# POWER_IN.net
KiCad netlist of a schematic drawn in Altium Designer
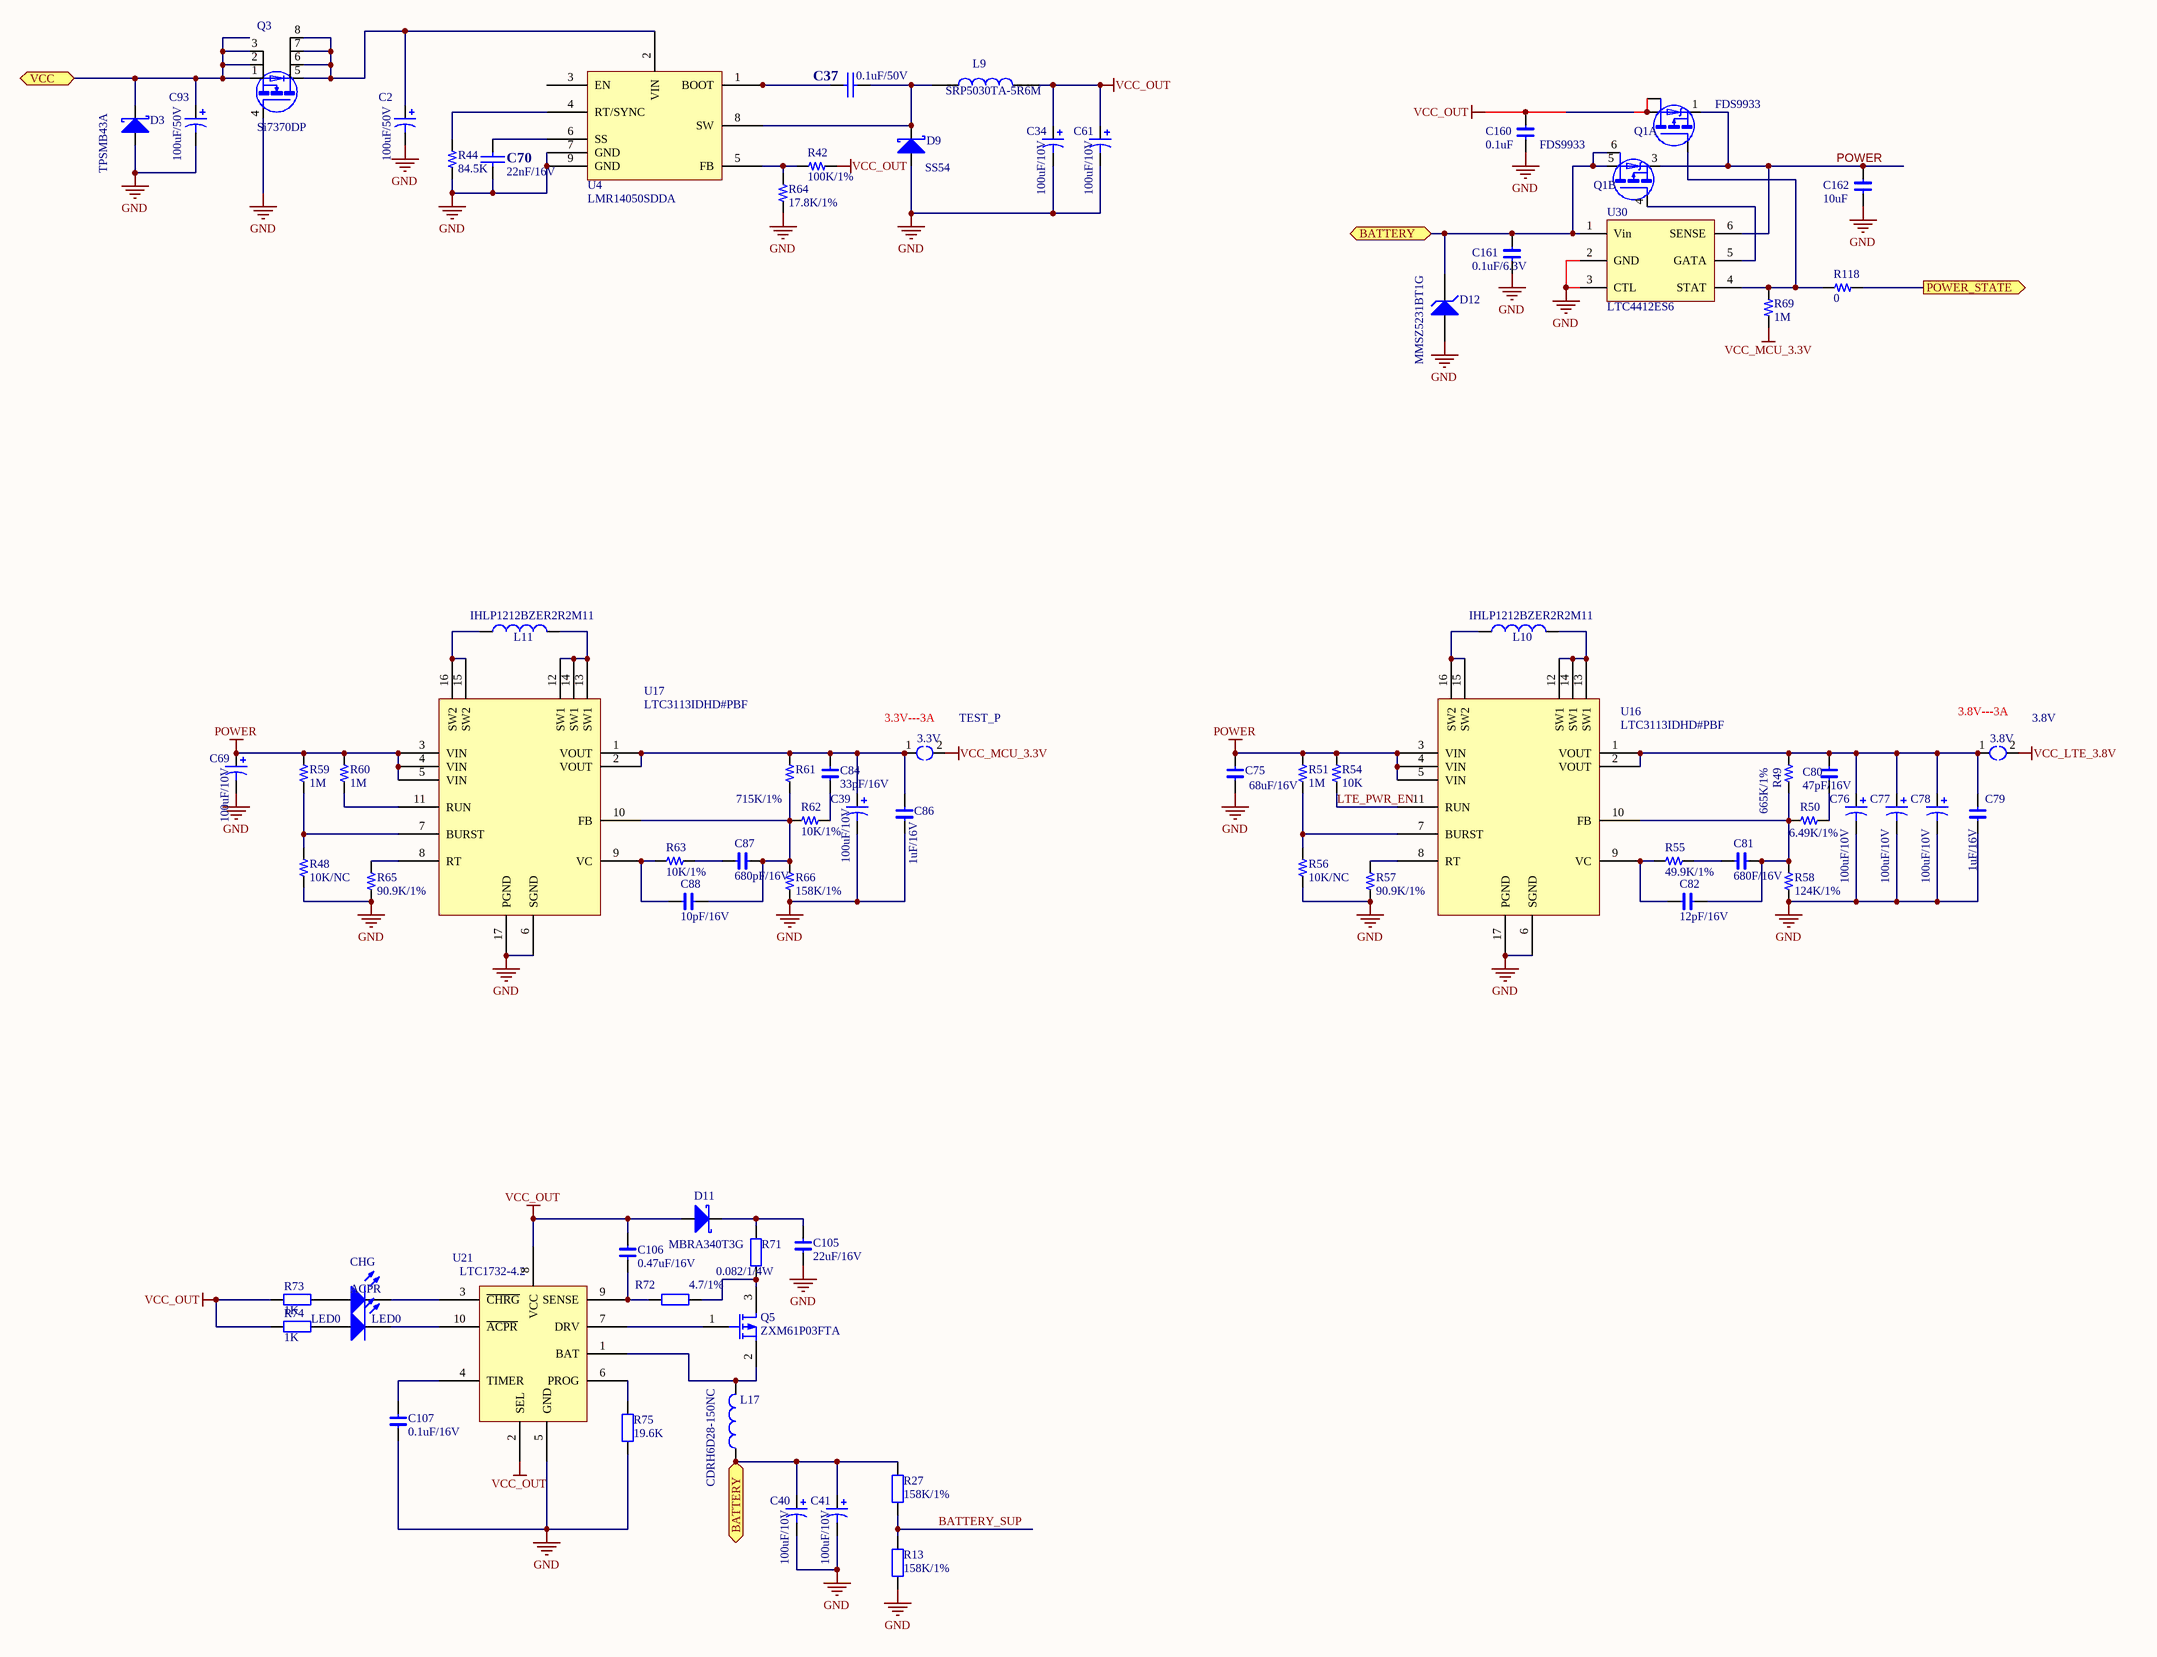
[diagram p0: POWER_IN.SchDoc]

(export (version "E")
  (design (tool "Eeschema 10.0.6"))
  (components
    (comp (ref "3.3V")
      (value "TEST_P")
      (footprint "Pcblib_20110825:TP_High PWR")
      (libsource (lib "Schlib_20110825") (part "TEST_P"))
    )
    (comp (ref "3.8V")
      (value "3.8V")
      (footprint "Pcblib_20110825:TP_High PWR")
      (description "TEST_P")
      (libsource (lib "Schlib_20110825") (part "TEST_P"))
    )
    (comp (ref "ACPR")
      (value "LED0")
      (footprint "0603LED")
      (description "Typical INFRARED GaAs LED")
      (fields (field (name "PUBLISHER") "Altium Limited"))
      (libsource (lib "Miscellaneous Devices") (part "LED0"))
    )
    (comp (ref "C2")
      (value "100uF/50V")
      (footprint "2220C")
      (description "Polarized Capacitor (Radial)")
      (fields (field (name "PUBLISHER") "Altium Limited"))
      (libsource (lib "Miscellaneous Devices") (part "Cap Pol1"))
    )
    (comp (ref "C34")
      (value "100uF/10V")
      (footprint "1210E")
      (description "Polarized Capacitor (Radial)")
      (fields (field (name "PUBLISHER") "Altium Limited"))
      (libsource (lib "Miscellaneous Devices") (part "Cap Pol1"))
    )
    (comp (ref "C37")
      (value "0.1uF/50V")
      (footprint "0603C")
      (description "Capacitor")
      (libsource (lib "*") (part "CAP"))
    )
    (comp (ref "C39")
      (value "100uF/10V")
      (footprint "1210E")
      (description "Polarized Capacitor (Radial)")
      (fields (field (name "PUBLISHER") "Altium Limited"))
      (libsource (lib "Miscellaneous Devices") (part "Cap Pol1"))
    )
    (comp (ref "C40")
      (value "100uF/10V")
      (footprint "1210E")
      (description "Polarized Capacitor (Radial)")
      (fields (field (name "PUBLISHER") "Altium Limited"))
      (libsource (lib "Miscellaneous Devices") (part "Cap Pol1"))
    )
    (comp (ref "C41")
      (value "100uF/10V")
      (footprint "1210E")
      (description "Polarized Capacitor (Radial)")
      (fields (field (name "PUBLISHER") "Altium Limited"))
      (libsource (lib "Miscellaneous Devices") (part "Cap Pol1"))
    )
    (comp (ref "C61")
      (value "100uF/10V")
      (footprint "1210E")
      (description "Polarized Capacitor (Radial)")
      (fields (field (name "PUBLISHER") "Altium Limited"))
      (libsource (lib "Miscellaneous Devices") (part "Cap Pol1"))
    )
    (comp (ref "C69")
      (value "100uF/10V")
      (footprint "1210E")
      (description "Polarized Capacitor (Radial)")
      (fields (field (name "PUBLISHER") "Altium Limited"))
      (libsource (lib "Miscellaneous Devices") (part "Cap Pol1"))
    )
    (comp (ref "C70")
      (value "22nF/16V")
      (footprint "0603C")
      (description "Capacitor")
      (libsource (lib "*") (part "CAP"))
    )
    (comp (ref "C75")
      (value "68uF/16V")
      (footprint "1206C")
      (description "C")
      (libsource (lib "Top") (part "C"))
    )
    (comp (ref "C76")
      (value "100uF/10V")
      (footprint "1210E")
      (description "Polarized Capacitor (Radial)")
      (fields (field (name "PUBLISHER") "Altium Limited"))
      (libsource (lib "Miscellaneous Devices") (part "Cap Pol1"))
    )
    (comp (ref "C77")
      (value "100uF/10V")
      (footprint "1210E")
      (description "Polarized Capacitor (Radial)")
      (fields (field (name "PUBLISHER") "Altium Limited"))
      (libsource (lib "Miscellaneous Devices") (part "Cap Pol1"))
    )
    (comp (ref "C78")
      (value "100uF/10V")
      (footprint "1210E")
      (description "Polarized Capacitor (Radial)")
      (fields (field (name "PUBLISHER") "Altium Limited"))
      (libsource (lib "Miscellaneous Devices") (part "Cap Pol1"))
    )
    (comp (ref "C79")
      (value "1uF/16V")
      (footprint "0603C")
      (description "C")
      (libsource (lib "Top") (part "C"))
    )
    (comp (ref "C80")
      (value "47pF/16V")
      (footprint "0603C")
      (description "C")
      (libsource (lib "Top") (part "C"))
    )
    (comp (ref "C81")
      (value "680F/16V")
      (footprint "0603C")
      (description "C")
      (libsource (lib "Top") (part "C"))
    )
    (comp (ref "C82")
      (value "12pF/16V")
      (footprint "0603C")
      (description "C")
      (libsource (lib "Top") (part "C"))
    )
    (comp (ref "C84")
      (value "33pF/16V")
      (footprint "0603C")
      (description "C")
      (libsource (lib "Top") (part "C"))
    )
    (comp (ref "C86")
      (value "1uF/16V")
      (footprint "0603C")
      (description "C")
      (libsource (lib "Top") (part "C"))
    )
    (comp (ref "C87")
      (value "680pF/16V")
      (footprint "0603C")
      (description "C")
      (libsource (lib "Top") (part "C"))
    )
    (comp (ref "C88")
      (value "10pF/16V")
      (footprint "0603C")
      (description "C")
      (libsource (lib "Top") (part "C"))
    )
    (comp (ref "C93")
      (value "100uF/50V")
      (footprint "2220C")
      (description "Polarized Capacitor (Radial)")
      (fields (field (name "PUBLISHER") "Altium Limited"))
      (libsource (lib "Miscellaneous Devices") (part "Cap Pol1"))
    )
    (comp (ref "C105")
      (value "22uF/16V")
      (footprint "0805C")
      (description "C")
      (libsource (lib "Top") (part "C"))
    )
    (comp (ref "C106")
      (value "0.47uF/16V")
      (footprint "0603C")
      (description "C")
      (libsource (lib "Top") (part "C"))
    )
    (comp (ref "C107")
      (value "0.1uF/16V")
      (footprint "0603C")
      (description "C")
      (libsource (lib "Top") (part "C"))
    )
    (comp (ref "C160") (value "0.1uF") (footprint "0603C") (description "C") (libsource (lib "*") (part "C")))
    (comp (ref "C161")
      (value "0.1uF/6.3V")
      (footprint "0603C")
      (description "C")
      (libsource (lib "*") (part "C"))
    )
    (comp (ref "C162") (value "10uF") (footprint "0603C") (description "C") (libsource (lib "*") (part "C")))
    (comp (ref "CHG")
      (value "LED0")
      (footprint "0603LED")
      (description "Typical INFRARED GaAs LED")
      (fields (field (name "PUBLISHER") "Altium Limited"))
      (libsource (lib "Miscellaneous Devices") (part "LED0"))
    )
    (comp (ref "D3")
      (value "TPSMB43A")
      (footprint "Pcblib_20110825:SMB")
      (description "Schottky Diode")
      (libsource (lib "*") (part "DIODE S"))
    )
    (comp (ref "D9")
      (value "SS54")
      (footprint "SMa")
      (description "Schottky Diode")
      (libsource (lib "*") (part "DIODE S"))
    )
    (comp (ref "D11")
      (value "MBRA340T3G")
      (footprint "SMA")
      (description "Schottky Diode")
      (libsource (lib "*") (part "DIODE S"))
    )
    (comp (ref "D12")
      (value "MMSZ5231BT1G")
      (footprint "Pcblib_20110825:SOD123")
      (description "Zener Diode")
      (fields (field (name "PUBLISHER") "Altium Limited"))
      (libsource (lib "Miscellaneous Devices") (part "D Zener"))
    )
    (comp (ref "L9") (value "SRP5030TA-5R6M") (footprint "SRP5030T") (libsource (lib "*") (part "INDUCTOR")))
    (comp (ref "L10")
      (value "IHLP1212BZER2R2M11")
      (footprint "Pcblib_20110825:IHLP-1212BZ")
      (description "Inductor")
      (fields (field (name "PUBLISHER") "Altium Limited"))
      (libsource (lib "Miscellaneous Devices") (part "Inductor"))
    )
    (comp (ref "L11")
      (value "IHLP1212BZER2R2M11")
      (footprint "Pcblib_20110825:IHLP-1212BZ")
      (description "Inductor")
      (fields (field (name "PUBLISHER") "Altium Limited"))
      (libsource (lib "Miscellaneous Devices") (part "Inductor"))
    )
    (comp (ref "L17")
      (value "CDRH6D28-150NC")
      (footprint "Pcblib_20110825:CDRH6D23")
      (description "Inductor")
      (fields (field (name "PUBLISHER") "Altium Limited"))
      (libsource (lib "Miscellaneous Devices") (part "Inductor"))
    )
    (comp (ref "Q1") (value "FDS9933") (footprint "FDS9933") (libsource (lib "*") (part "FDS4935")))
    (comp (ref "Q3")
      (value "Si7370DP")
      (footprint "PowerPAK SO-8")
      (libsource (lib "stm32") (part "BSC070N1ONS3"))
    )
    (comp (ref "Q5")
      (value "ZXM61P03FTA")
      (footprint "SOT23-3")
      (description "ZXM61P03F")
      (fields (field (name "PUBLISHER") "Altium Limited"))
      (libsource (lib "Miscellaneous Devices") (part "MOSFET-P"))
    )
    (comp (ref "R13")
      (value "158K/1%")
      (footprint "0603R")
      (description "Resistor")
      (fields (field (name "PUBLISHER") "Altium Limited"))
      (libsource (lib "") (part "Res2_1"))
    )
    (comp (ref "R27")
      (value "158K/1%")
      (footprint "0603R")
      (description "Resistor")
      (fields (field (name "PUBLISHER") "Altium Limited"))
      (libsource (lib "") (part "Res2_1"))
    )
    (comp (ref "R42")
      (value "100K/1%")
      (footprint "0603R")
      (description "R")
      (libsource (lib "JRJ_1") (part "R"))
    )
    (comp (ref "R44")
      (value "84.5K")
      (footprint "0603R")
      (description "R")
      (libsource (lib "JRJ_1") (part "R"))
    )
    (comp (ref "R48")
      (value "10K/NC")
      (footprint "0603R")
      (description "R")
      (libsource (lib "JRJ_1") (part "R"))
    )
    (comp (ref "R49")
      (value "665K/1%")
      (footprint "0603R")
      (description "R")
      (libsource (lib "JRJ_1") (part "R"))
    )
    (comp (ref "R50")
      (value "6.49K/1%")
      (footprint "0603R")
      (description "R")
      (libsource (lib "JRJ_1") (part "R"))
    )
    (comp (ref "R51") (value "1M") (footprint "0603R") (description "R") (libsource (lib "JRJ_1") (part "R")))
    (comp (ref "R54")
      (value "10K")
      (footprint "0603R")
      (description "R")
      (libsource (lib "JRJ_1") (part "R"))
    )
    (comp (ref "R55")
      (value "49.9K/1%")
      (footprint "0603R")
      (description "R")
      (libsource (lib "JRJ_1") (part "R"))
    )
    (comp (ref "R56")
      (value "10K/NC")
      (footprint "0603R")
      (description "R")
      (libsource (lib "JRJ_1") (part "R"))
    )
    (comp (ref "R57")
      (value "90.9K/1%")
      (footprint "0603R")
      (description "R")
      (libsource (lib "JRJ_1") (part "R"))
    )
    (comp (ref "R58")
      (value "124K/1%")
      (footprint "0603R")
      (description "R")
      (libsource (lib "JRJ_1") (part "R"))
    )
    (comp (ref "R59") (value "1M") (footprint "0603R") (description "R") (libsource (lib "JRJ_1") (part "R")))
    (comp (ref "R60") (value "1M") (footprint "0603R") (description "R") (libsource (lib "JRJ_1") (part "R")))
    (comp (ref "R61")
      (value "715K/1%")
      (footprint "0603R")
      (description "R")
      (libsource (lib "JRJ_1") (part "R"))
    )
    (comp (ref "R62")
      (value "10K/1%")
      (footprint "0603R")
      (description "R")
      (libsource (lib "JRJ_1") (part "R"))
    )
    (comp (ref "R63")
      (value "10K/1%")
      (footprint "0603R")
      (description "R")
      (libsource (lib "JRJ_1") (part "R"))
    )
    (comp (ref "R64")
      (value "17.8K/1%")
      (footprint "0603R")
      (description "R")
      (libsource (lib "JRJ_1") (part "R"))
    )
    (comp (ref "R65")
      (value "90.9K/1%")
      (footprint "0603R")
      (description "R")
      (libsource (lib "JRJ_1") (part "R"))
    )
    (comp (ref "R66")
      (value "158K/1%")
      (footprint "0603R")
      (description "R")
      (libsource (lib "JRJ_1") (part "R"))
    )
    (comp (ref "R69") (value "1M") (footprint "0603R") (description "R") (libsource (lib "*") (part "R")))
    (comp (ref "R71")
      (value "0.082/1/4W")
      (footprint "2010R")
      (description "Resistor")
      (fields (field (name "PUBLISHER") "Altium Limited"))
      (libsource (lib "") (part "Res2_1"))
    )
    (comp (ref "R72")
      (value "4.7/1%")
      (footprint "0603R")
      (description "Resistor")
      (fields (field (name "PUBLISHER") "Altium Limited"))
      (libsource (lib "Miscellaneous Devices") (part "Res2"))
    )
    (comp (ref "R73")
      (value "1K")
      (footprint "0603R")
      (description "Resistor")
      (fields (field (name "PUBLISHER") "Altium Limited"))
      (libsource (lib "") (part "Res2_2"))
    )
    (comp (ref "R74")
      (value "1K")
      (footprint "0603R")
      (description "Resistor")
      (fields (field (name "PUBLISHER") "Altium Limited"))
      (libsource (lib "") (part "Res2_2"))
    )
    (comp (ref "R75")
      (value "19.6K")
      (footprint "0603R")
      (description "Resistor")
      (fields (field (name "PUBLISHER") "Altium Limited"))
      (libsource (lib "") (part "Res2_1"))
    )
    (comp (ref "R118") (value "0") (footprint "0603R") (description "R") (libsource (lib "") (part "R_1")))
    (comp (ref "U4")
      (value "LMR14050SDDA")
      (footprint "SOP127P600X168_HS-8N")
      (libsource (lib "Schlib_20110825") (part "LMR14050SDDA"))
    )
    (comp (ref "U16")
      (value "LTC3113IDHD#PBF")
      (footprint "QFN50P400X500X80-16N")
      (libsource (lib "Schlib_20110825") (part "LTC3113IDHD#PBF"))
    )
    (comp (ref "U17")
      (value "LTC3113IDHD#PBF")
      (footprint "QFN50P400X500X80-16N")
      (libsource (lib "Schlib_20110825") (part "LTC3113IDHD#PBF"))
    )
    (comp (ref "U21")
      (value "LTC1732-4.2")
      (footprint "MSOP-10")
      (libsource (lib "Schlib_20110825") (part "LTC1732-4.2"))
    )
    (comp (ref "U30") (value "LTC4412ES6") (footprint "TSOT-23") (libsource (lib "*") (part "LTC4412")))
  )
  (nets
    (net (code "1") (name "/BATTERY") (class "Default")
      (node (ref "C161") (pin "2") (pintype "passive"))
      (node (ref "C40") (pin "1") (pinfunction "1_1") (pintype "passive"))
      (node (ref "C41") (pin "1") (pinfunction "1_1") (pintype "passive"))
      (node (ref "D12") (pin "K") (pinfunction "K_K") (pintype "passive"))
      (node (ref "L17") (pin "1") (pinfunction "1_1") (pintype "passive"))
      (node (ref "Q1") (pin "5") (pinfunction "D_5") (pintype "passive"))
      (node (ref "R27") (pin "2") (pinfunction "2_2") (pintype "passive"))
      (node (ref "U30") (pin "1") (pinfunction "Vin_1") (pintype "passive"))
    )
    (net (code "2") (name "/BATTERY_SUP") (class "Default")
      (node (ref "R13") (pin "2") (pinfunction "2_2") (pintype "passive"))
      (node (ref "R27") (pin "1") (pinfunction "1_1") (pintype "passive"))
    )
    (net (code "3") (name "/LTE_PWR_EN") (class "Default")
      (node (ref "R54") (pin "2") (pintype "passive"))
      (node (ref "U16") (pin "11") (pinfunction "RUN_11") (pintype "passive"))
    )
    (net (code "4") (name "/POWER_STATE") (class "Default") (node (ref "R118") (pin "2") (pintype "passive")))
    (net (code "5") (name "/VCC") (class "Default")
      (node (ref "C93") (pin "1") (pinfunction "1_1") (pintype "passive"))
      (node (ref "D3") (pin "2") (pinfunction "K_2") (pintype "passive"))
      (node (ref "Q3") (pin "1") (pinfunction "D_1") (pintype "passive"))
      (node (ref "Q3") (pin "2") (pinfunction "D_2") (pintype "passive"))
      (node (ref "Q3") (pin "3") (pinfunction "D_3") (pintype "passive"))
    )
    (net (code "6") (name "GND") (class "Default")
      (node (ref "C105") (pin "1") (pintype "passive"))
      (node (ref "C107") (pin "1") (pintype "passive"))
      (node (ref "C160") (pin "1") (pintype "passive"))
      (node (ref "C161") (pin "1") (pintype "passive"))
      (node (ref "C162") (pin "1") (pintype "passive"))
      (node (ref "C2") (pin "2") (pinfunction "2_2") (pintype "passive"))
      (node (ref "C34") (pin "2") (pinfunction "2_2") (pintype "passive"))
      (node (ref "C39") (pin "2") (pinfunction "2_2") (pintype "passive"))
      (node (ref "C40") (pin "2") (pinfunction "2_2") (pintype "passive"))
      (node (ref "C41") (pin "2") (pinfunction "2_2") (pintype "passive"))
      (node (ref "C61") (pin "2") (pinfunction "2_2") (pintype "passive"))
      (node (ref "C69") (pin "2") (pinfunction "2_2") (pintype "passive"))
      (node (ref "C70") (pin "2") (pinfunction "2_2") (pintype "passive"))
      (node (ref "C75") (pin "2") (pintype "passive"))
      (node (ref "C76") (pin "2") (pinfunction "2_2") (pintype "passive"))
      (node (ref "C77") (pin "2") (pinfunction "2_2") (pintype "passive"))
      (node (ref "C78") (pin "2") (pinfunction "2_2") (pintype "passive"))
      (node (ref "C79") (pin "2") (pintype "passive"))
      (node (ref "C86") (pin "2") (pintype "passive"))
      (node (ref "C93") (pin "2") (pinfunction "2_2") (pintype "passive"))
      (node (ref "D12") (pin "A") (pinfunction "A_A") (pintype "passive"))
      (node (ref "D3") (pin "1") (pinfunction "A_1") (pintype "passive"))
      (node (ref "D9") (pin "1") (pinfunction "A_1") (pintype "passive"))
      (node (ref "Q3") (pin "4") (pinfunction "G_4") (pintype "passive"))
      (node (ref "R13") (pin "1") (pinfunction "1_1") (pintype "passive"))
      (node (ref "R44") (pin "1") (pintype "passive"))
      (node (ref "R48") (pin "2") (pintype "passive"))
      (node (ref "R56") (pin "2") (pintype "passive"))
      (node (ref "R57") (pin "2") (pintype "passive"))
      (node (ref "R58") (pin "1") (pintype "passive"))
      (node (ref "R64") (pin "2") (pintype "passive"))
      (node (ref "R65") (pin "2") (pintype "passive"))
      (node (ref "R66") (pin "1") (pintype "passive"))
      (node (ref "R75") (pin "1") (pinfunction "1_1") (pintype "passive"))
      (node (ref "U16") (pin "17") (pinfunction "PGND_17") (pintype "passive"))
      (node (ref "U16") (pin "6") (pinfunction "SGND_6") (pintype "passive"))
      (node (ref "U17") (pin "17") (pinfunction "PGND_17") (pintype "passive"))
      (node (ref "U17") (pin "6") (pinfunction "SGND_6") (pintype "passive"))
      (node (ref "U21") (pin "5") (pinfunction "GND_5") (pintype "passive"))
      (node (ref "U30") (pin "2") (pinfunction "GND_2") (pintype "passive"))
      (node (ref "U30") (pin "3") (pinfunction "CTL_3") (pintype "passive"))
      (node (ref "U4") (pin "7") (pinfunction "GND_7") (pintype "passive"))
      (node (ref "U4") (pin "9") (pinfunction "GND_9") (pintype "passive"))
    )
    (net (code "7") (name "Net-(3.3V-Pad1)") (class "Default")
      (node (ref "3.3V") (pin "1") (pinfunction "1_1") (pintype "passive"))
      (node (ref "C39") (pin "1") (pinfunction "1_1") (pintype "passive"))
      (node (ref "C84") (pin "1") (pintype "passive"))
      (node (ref "C86") (pin "1") (pintype "passive"))
      (node (ref "R61") (pin "2") (pintype "passive"))
      (node (ref "U17") (pin "1") (pinfunction "VOUT_1") (pintype "passive"))
      (node (ref "U17") (pin "2") (pinfunction "VOUT_2") (pintype "passive"))
    )
    (net (code "8") (name "Net-(3.8V-Pad1)") (class "Default")
      (node (ref "3.8V") (pin "1") (pinfunction "1_1") (pintype "passive"))
      (node (ref "C76") (pin "1") (pinfunction "1_1") (pintype "passive"))
      (node (ref "C77") (pin "1") (pinfunction "1_1") (pintype "passive"))
      (node (ref "C78") (pin "1") (pinfunction "1_1") (pintype "passive"))
      (node (ref "C79") (pin "1") (pintype "passive"))
      (node (ref "C80") (pin "1") (pintype "passive"))
      (node (ref "R49") (pin "2") (pintype "passive"))
      (node (ref "U16") (pin "1") (pinfunction "VOUT_1") (pintype "passive"))
      (node (ref "U16") (pin "2") (pinfunction "VOUT_2") (pintype "passive"))
    )
    (net (code "9") (name "Net-(ACPR-A)") (class "Default")
      (node (ref "ACPR") (pin "1") (pinfunction "A_1") (pintype "passive"))
      (node (ref "R74") (pin "2") (pinfunction "2_2") (pintype "passive"))
    )
    (net (code "10") (name "Net-(ACPR-K)") (class "Default")
      (node (ref "ACPR") (pin "2") (pinfunction "K_2") (pintype "passive"))
      (node (ref "U21") (pin "10") (pinfunction "~{ACPR}_10") (pintype "passive"))
    )
    (net (code "11") (name "Net-(C80-Pad2)") (class "Default")
      (node (ref "C80") (pin "2") (pintype "passive"))
      (node (ref "R50") (pin "1") (pintype "passive"))
    )
    (net (code "12") (name "Net-(C81-Pad1)") (class "Default")
      (node (ref "C81") (pin "1") (pintype "passive"))
      (node (ref "R55") (pin "1") (pintype "passive"))
    )
    (net (code "13") (name "Net-(C84-Pad2)") (class "Default")
      (node (ref "C84") (pin "2") (pintype "passive"))
      (node (ref "R62") (pin "1") (pintype "passive"))
    )
    (net (code "14") (name "Net-(C87-Pad1)") (class "Default")
      (node (ref "C87") (pin "1") (pintype "passive"))
      (node (ref "R63") (pin "1") (pintype "passive"))
    )
    (net (code "15") (name "Net-(CHG-A)") (class "Default")
      (node (ref "CHG") (pin "1") (pinfunction "A_1") (pintype "passive"))
      (node (ref "R73") (pin "2") (pinfunction "2_2") (pintype "passive"))
    )
    (net (code "16") (name "Net-(CHG-K)") (class "Default")
      (node (ref "CHG") (pin "2") (pinfunction "K_2") (pintype "passive"))
      (node (ref "U21") (pin "3") (pinfunction "~{CHRG}_3") (pintype "passive"))
    )
    (net (code "17") (name "Net-(D9-K)") (class "Default")
      (node (ref "C37") (pin "1") (pinfunction "1_1") (pintype "passive"))
      (node (ref "D9") (pin "2") (pinfunction "K_2") (pintype "passive"))
      (node (ref "L9") (pin "1") (pinfunction "1_1") (pintype "passive"))
      (node (ref "U4") (pin "8") (pinfunction "SW_8") (pintype "passive"))
    )
    (net (code "18") (name "Net-(D11-K)") (class "Default")
      (node (ref "C105") (pin "2") (pintype "passive"))
      (node (ref "D11") (pin "2") (pinfunction "K_2") (pintype "passive"))
      (node (ref "R71") (pin "2") (pinfunction "2_2") (pintype "passive"))
    )
    (net (code "19") (name "Net-(L10-Pad1)") (class "Default")
      (node (ref "L10") (pin "1") (pinfunction "1_1") (pintype "passive"))
      (node (ref "U16") (pin "15") (pinfunction "SW2_15") (pintype "passive"))
      (node (ref "U16") (pin "16") (pinfunction "SW2_16") (pintype "passive"))
    )
    (net (code "20") (name "Net-(L10-Pad2)") (class "Default")
      (node (ref "L10") (pin "2") (pinfunction "2_2") (pintype "passive"))
      (node (ref "U16") (pin "12") (pinfunction "SW1_12") (pintype "passive"))
      (node (ref "U16") (pin "13") (pinfunction "SW1_13") (pintype "passive"))
      (node (ref "U16") (pin "14") (pinfunction "SW1_14") (pintype "passive"))
    )
    (net (code "21") (name "Net-(L11-Pad1)") (class "Default")
      (node (ref "L11") (pin "1") (pinfunction "1_1") (pintype "passive"))
      (node (ref "U17") (pin "15") (pinfunction "SW2_15") (pintype "passive"))
      (node (ref "U17") (pin "16") (pinfunction "SW2_16") (pintype "passive"))
    )
    (net (code "22") (name "Net-(L11-Pad2)") (class "Default")
      (node (ref "L11") (pin "2") (pinfunction "2_2") (pintype "passive"))
      (node (ref "U17") (pin "12") (pinfunction "SW1_12") (pintype "passive"))
      (node (ref "U17") (pin "13") (pinfunction "SW1_13") (pintype "passive"))
      (node (ref "U17") (pin "14") (pinfunction "SW1_14") (pintype "passive"))
    )
    (net (code "23") (name "Net-(Q1A-G)") (class "Default")
      (node (ref "Q1") (pin "2") (pinfunction "G_2") (pintype "passive"))
      (node (ref "R118") (pin "1") (pintype "passive"))
      (node (ref "R69") (pin "1") (pintype "passive"))
      (node (ref "U30") (pin "4") (pinfunction "STAT_4") (pintype "passive"))
    )
    (net (code "24") (name "Net-(Q1B-G)") (class "Default")
      (node (ref "Q1") (pin "4") (pinfunction "G_4") (pintype "passive"))
      (node (ref "U30") (pin "5") (pinfunction "GATA_5") (pintype "passive"))
    )
    (net (code "25") (name "Net-(Q3-S)") (class "Default")
      (node (ref "C2") (pin "1") (pinfunction "1_1") (pintype "passive"))
      (node (ref "Q3") (pin "5") (pinfunction "S_5") (pintype "passive"))
      (node (ref "Q3") (pin "6") (pinfunction "D_6") (pintype "passive"))
      (node (ref "Q3") (pin "7") (pinfunction "D1_7") (pintype "passive"))
      (node (ref "Q3") (pin "8") (pinfunction "D1_8") (pintype "passive"))
      (node (ref "U4") (pin "2") (pinfunction "VIN_2") (pintype "passive"))
    )
    (net (code "26") (name "Net-(Q5-D)") (class "Default")
      (node (ref "L17") (pin "2") (pinfunction "2_2") (pintype "passive"))
      (node (ref "Q5") (pin "2") (pinfunction "D_2") (pintype "passive"))
      (node (ref "U21") (pin "1") (pinfunction "BAT_1") (pintype "passive"))
    )
    (net (code "27") (name "Net-(Q5-G)") (class "Default")
      (node (ref "Q5") (pin "1") (pinfunction "G_1") (pintype "passive"))
      (node (ref "U21") (pin "7") (pinfunction "DRV_7") (pintype "passive"))
    )
    (net (code "28") (name "Net-(Q5-S)") (class "Default")
      (node (ref "Q5") (pin "3") (pinfunction "S_3") (pintype "passive"))
      (node (ref "R71") (pin "1") (pinfunction "1_1") (pintype "passive"))
      (node (ref "R72") (pin "1") (pinfunction "1_1") (pintype "passive"))
    )
    (net (code "29") (name "Net-(U4-BOOT)") (class "Default")
      (node (ref "C37") (pin "2") (pinfunction "2_2") (pintype "passive"))
      (node (ref "U4") (pin "1") (pinfunction "BOOT_1") (pintype "passive"))
    )
    (net (code "30") (name "Net-(U4-FB)") (class "Default")
      (node (ref "R42") (pin "1") (pintype "passive"))
      (node (ref "R64") (pin "1") (pintype "passive"))
      (node (ref "U4") (pin "5") (pinfunction "FB_5") (pintype "passive"))
    )
    (net (code "31") (name "Net-(U4-RT{slash}SYNC)") (class "Default")
      (node (ref "R44") (pin "2") (pintype "passive"))
      (node (ref "U4") (pin "4") (pinfunction "RT/SYNC_4") (pintype "passive"))
    )
    (net (code "32") (name "Net-(U4-SS)") (class "Default")
      (node (ref "C70") (pin "1") (pinfunction "1_1") (pintype "passive"))
      (node (ref "U4") (pin "6") (pinfunction "SS_6") (pintype "passive"))
    )
    (net (code "33") (name "Net-(U16-BURST)") (class "Default")
      (node (ref "R51") (pin "2") (pintype "passive"))
      (node (ref "R56") (pin "1") (pintype "passive"))
      (node (ref "U16") (pin "7") (pinfunction "BURST_7") (pintype "passive"))
    )
    (net (code "34") (name "Net-(U16-FB)") (class "Default")
      (node (ref "C81") (pin "2") (pintype "passive"))
      (node (ref "C82") (pin "2") (pintype "passive"))
      (node (ref "R49") (pin "1") (pintype "passive"))
      (node (ref "R50") (pin "2") (pintype "passive"))
      (node (ref "R58") (pin "2") (pintype "passive"))
      (node (ref "U16") (pin "10") (pinfunction "FB_10") (pintype "passive"))
    )
    (net (code "35") (name "Net-(U16-RT)") (class "Default")
      (node (ref "R57") (pin "1") (pintype "passive"))
      (node (ref "U16") (pin "8") (pinfunction "RT_8") (pintype "passive"))
    )
    (net (code "36") (name "Net-(U16-VC)") (class "Default")
      (node (ref "C82") (pin "1") (pintype "passive"))
      (node (ref "R55") (pin "2") (pintype "passive"))
      (node (ref "U16") (pin "9") (pinfunction "VC_9") (pintype "passive"))
    )
    (net (code "37") (name "Net-(U17-BURST)") (class "Default")
      (node (ref "R48") (pin "1") (pintype "passive"))
      (node (ref "R59") (pin "2") (pintype "passive"))
      (node (ref "U17") (pin "7") (pinfunction "BURST_7") (pintype "passive"))
    )
    (net (code "38") (name "Net-(U17-FB)") (class "Default")
      (node (ref "C87") (pin "2") (pintype "passive"))
      (node (ref "C88") (pin "2") (pintype "passive"))
      (node (ref "R61") (pin "1") (pintype "passive"))
      (node (ref "R62") (pin "2") (pintype "passive"))
      (node (ref "R66") (pin "2") (pintype "passive"))
      (node (ref "U17") (pin "10") (pinfunction "FB_10") (pintype "passive"))
    )
    (net (code "39") (name "Net-(U17-RT)") (class "Default")
      (node (ref "R65") (pin "1") (pintype "passive"))
      (node (ref "U17") (pin "8") (pinfunction "RT_8") (pintype "passive"))
    )
    (net (code "40") (name "Net-(U17-RUN)") (class "Default")
      (node (ref "R60") (pin "2") (pintype "passive"))
      (node (ref "U17") (pin "11") (pinfunction "RUN_11") (pintype "passive"))
    )
    (net (code "41") (name "Net-(U17-VC)") (class "Default")
      (node (ref "C88") (pin "1") (pintype "passive"))
      (node (ref "R63") (pin "2") (pintype "passive"))
      (node (ref "U17") (pin "9") (pinfunction "VC_9") (pintype "passive"))
    )
    (net (code "42") (name "Net-(U21-PROG)") (class "Default")
      (node (ref "R75") (pin "2") (pinfunction "2_2") (pintype "passive"))
      (node (ref "U21") (pin "6") (pinfunction "PROG_6") (pintype "passive"))
    )
    (net (code "43") (name "Net-(U21-SENSE)") (class "Default")
      (node (ref "C106") (pin "1") (pintype "passive"))
      (node (ref "R72") (pin "2") (pinfunction "2_2") (pintype "passive"))
      (node (ref "U21") (pin "9") (pinfunction "SENSE_9") (pintype "passive"))
    )
    (net (code "44") (name "Net-(U21-TIMER)") (class "Default")
      (node (ref "C107") (pin "2") (pintype "passive"))
      (node (ref "U21") (pin "4") (pinfunction "TIMER_4") (pintype "passive"))
    )
    (net (code "45") (name "POWER") (class "Default")
      (node (ref "C162") (pin "2") (pintype "passive"))
      (node (ref "C69") (pin "1") (pinfunction "1_1") (pintype "passive"))
      (node (ref "C75") (pin "1") (pintype "passive"))
      (node (ref "Q1") (pin "1") (pinfunction "S_1") (pintype "passive"))
      (node (ref "Q1") (pin "3") (pinfunction "S_3") (pintype "passive"))
      (node (ref "R51") (pin "1") (pintype "passive"))
      (node (ref "R54") (pin "1") (pintype "passive"))
      (node (ref "R59") (pin "1") (pintype "passive"))
      (node (ref "R60") (pin "1") (pintype "passive"))
      (node (ref "U16") (pin "3") (pinfunction "VIN_3") (pintype "passive"))
      (node (ref "U16") (pin "4") (pinfunction "VIN_4") (pintype "passive"))
      (node (ref "U16") (pin "5") (pinfunction "VIN_5") (pintype "passive"))
      (node (ref "U17") (pin "3") (pinfunction "VIN_3") (pintype "passive"))
      (node (ref "U17") (pin "4") (pinfunction "VIN_4") (pintype "passive"))
      (node (ref "U17") (pin "5") (pinfunction "VIN_5") (pintype "passive"))
      (node (ref "U30") (pin "6") (pinfunction "SENSE_6") (pintype "passive"))
    )
    (net (code "46") (name "VCC_LTE_3.8V") (class "Default")
      (node (ref "3.8V") (pin "2") (pinfunction "2_2") (pintype "passive"))
    )
    (net (code "47") (name "VCC_MCU_3.3V") (class "Default")
      (node (ref "3.3V") (pin "2") (pinfunction "2_2") (pintype "passive"))
      (node (ref "R69") (pin "2") (pintype "passive"))
    )
    (net (code "48") (name "VCC_OUT") (class "Default")
      (node (ref "C106") (pin "2") (pintype "passive"))
      (node (ref "C160") (pin "2") (pintype "passive"))
      (node (ref "C34") (pin "1") (pinfunction "1_1") (pintype "passive"))
      (node (ref "C61") (pin "1") (pinfunction "1_1") (pintype "passive"))
      (node (ref "D11") (pin "1") (pinfunction "A_1") (pintype "passive"))
      (node (ref "L9") (pin "2") (pinfunction "2_2") (pintype "passive"))
      (node (ref "Q1") (pin "7") (pinfunction "D_7") (pintype "passive"))
      (node (ref "Q1") (pin "8") (pinfunction "D_8") (pintype "passive"))
      (node (ref "R42") (pin "2") (pintype "passive"))
      (node (ref "R73") (pin "1") (pinfunction "1_1") (pintype "passive"))
      (node (ref "R74") (pin "1") (pinfunction "1_1") (pintype "passive"))
      (node (ref "U21") (pin "2") (pinfunction "SEL_2") (pintype "passive"))
      (node (ref "U21") (pin "8") (pinfunction "VCC_8") (pintype "passive"))
    )
    (net (code "49") (name "unconnected-(Q1B-D-Pad6)") (class "Default")
      (node (ref "Q1") (pin "6") (pinfunction "D_6") (pintype "passive"))
    )
    (net (code "50") (name "unconnected-(U4-EN-Pad3)") (class "Default")
      (node (ref "U4") (pin "3") (pinfunction "EN_3") (pintype "passive"))
    )
  )
)
